# DRIVE_MOTORS.net
KiCad netlist of a schematic drawn in Altium Designer
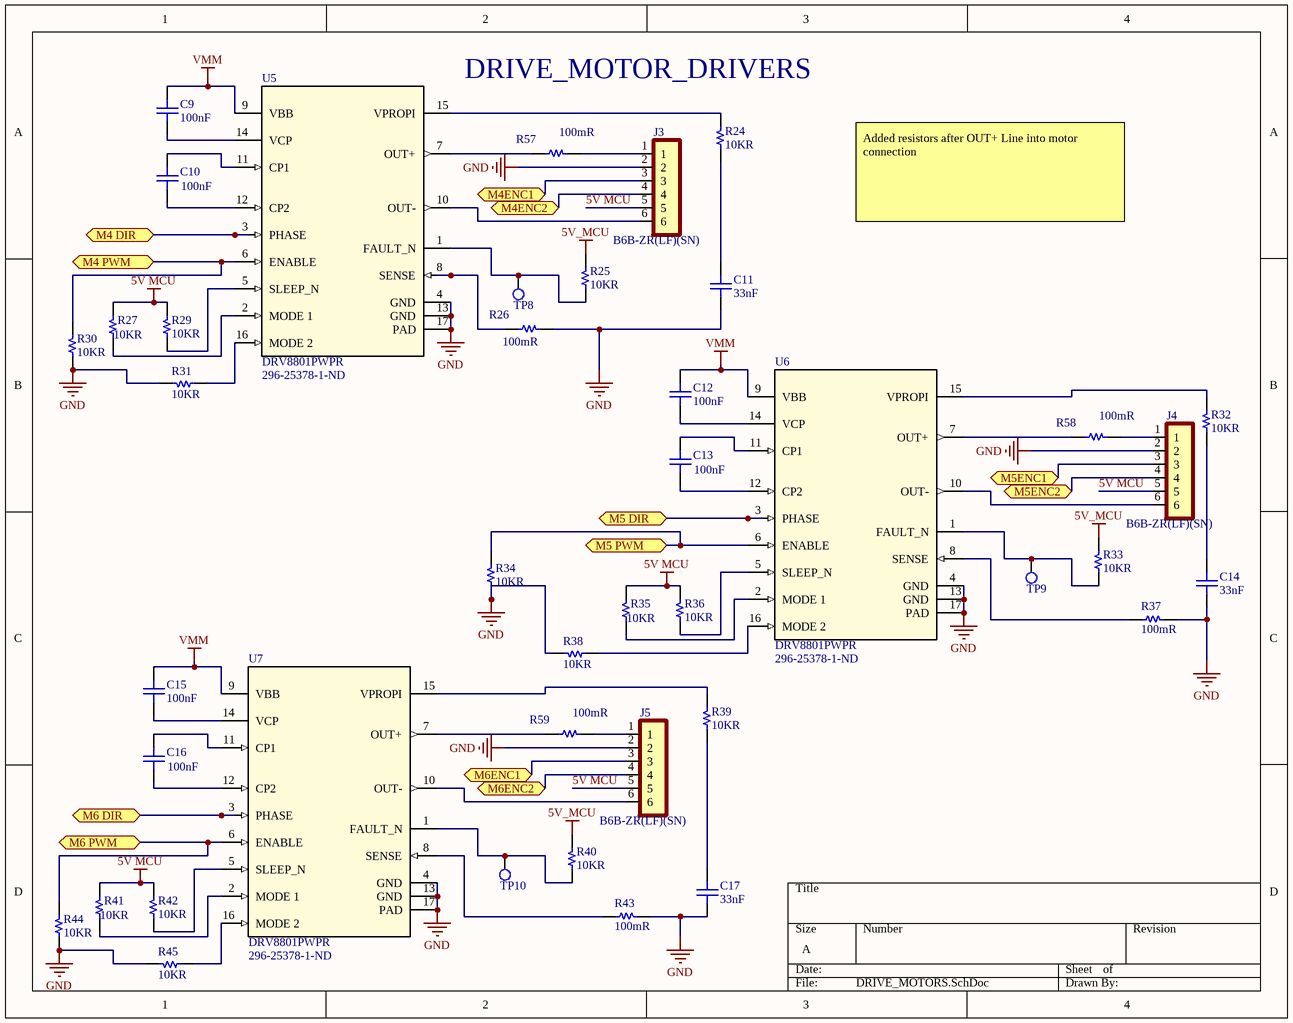
[diagram p0: DRIVE_MOTORS.SchDoc]

(export (version "E")
  (design (tool "Eeschema 10.0.6"))
  (components
    (comp (ref "C9")
      (value "100nF")
      (footprint "CAP_ADJ_0805")
      (description "CERAMIC CAPACITOR SMD 0805")
      (fields
        (field (name "MANUFACTURER") "KEMET")
        (field (name "MANUFACTURER PART NUMBER") "C0805C104J5RACAUTO")
      )
      (libsource (lib "ORI_MANIPULATOR_BRD") (part "CAP_ADJ_0805"))
    )
    (comp (ref "C10")
      (value "100nF")
      (footprint "CAP_ADJ_0805")
      (description "CERAMIC CAPACITOR SMD 0805")
      (fields
        (field (name "MANUFACTURER") "KEMET")
        (field (name "MANUFACTURER PART NUMBER") "C0805C104J5RACAUTO")
      )
      (libsource (lib "ORI_MANIPULATOR_BRD") (part "CAP_ADJ_0805"))
    )
    (comp (ref "C11")
      (value "33nF")
      (footprint "CAP_ADJ_0805")
      (description "CERAMIC CAPACITOR SMD 0805")
      (fields
        (field (name "MANUFACTURER") "Samsung")
        (field (name "MANUFACTURER PART NUMBER") "CL21B333JBANNNC")
      )
      (libsource (lib "ORI_MANIPULATOR_BRD") (part "CAP_ADJ_0805"))
    )
    (comp (ref "C12")
      (value "100nF")
      (footprint "CAP_ADJ_0805")
      (description "CERAMIC CAPACITOR SMD 0805")
      (fields
        (field (name "MANUFACTURER") "KEMET")
        (field (name "MANUFACTURER PART NUMBER") "C0805C104J5RACAUTO")
      )
      (libsource (lib "ORI_MANIPULATOR_BRD") (part "CAP_ADJ_0805"))
    )
    (comp (ref "C13")
      (value "100nF")
      (footprint "CAP_ADJ_0805")
      (description "CERAMIC CAPACITOR SMD 0805")
      (fields
        (field (name "MANUFACTURER") "KEMET")
        (field (name "MANUFACTURER PART NUMBER") "C0805C104J5RACAUTO")
      )
      (libsource (lib "ORI_MANIPULATOR_BRD") (part "CAP_ADJ_0805"))
    )
    (comp (ref "C14")
      (value "33nF")
      (footprint "CAP_ADJ_0805")
      (description "CERAMIC CAPACITOR SMD 0805")
      (fields
        (field (name "MANUFACTURER") "Samsung")
        (field (name "MANUFACTURER PART NUMBER") "CL21B333JBANNNC")
      )
      (libsource (lib "ORI_MANIPULATOR_BRD") (part "CAP_ADJ_0805"))
    )
    (comp (ref "C15")
      (value "100nF")
      (footprint "CAP_ADJ_0805")
      (description "CERAMIC CAPACITOR SMD 0805")
      (fields
        (field (name "MANUFACTURER") "KEMET")
        (field (name "MANUFACTURER PART NUMBER") "C0805C104J5RACAUTO")
      )
      (libsource (lib "ORI_MANIPULATOR_BRD") (part "CAP_ADJ_0805"))
    )
    (comp (ref "C16")
      (value "100nF")
      (footprint "CAP_ADJ_0805")
      (description "CERAMIC CAPACITOR SMD 0805")
      (fields
        (field (name "MANUFACTURER") "KEMET")
        (field (name "MANUFACTURER PART NUMBER") "C0805C104J5RACAUTO")
      )
      (libsource (lib "ORI_MANIPULATOR_BRD") (part "CAP_ADJ_0805"))
    )
    (comp (ref "C17")
      (value "33nF")
      (footprint "CAP_ADJ_0805")
      (description "CERAMIC CAPACITOR SMD 0805")
      (fields
        (field (name "MANUFACTURER") "Samsung")
        (field (name "MANUFACTURER PART NUMBER") "CL21B333JBANNNC")
      )
      (libsource (lib "ORI_MANIPULATOR_BRD") (part "CAP_ADJ_0805"))
    )
    (comp (ref "J3")
      (value "B6B-ZR(LF)(SN)")
      (footprint "SnapEDApcb:JST_B6B-ZR(LF)(SN)")
      (description "Connector Header Through Hole 6 position 0.059 _1.50mm_")
      (fields (field (name "MF") "JST Sales") (field (name "MP") "B6B-ZR_LF__SN_"))
      (libsource (lib "SnapEDAsch") (part "B6B-ZR(LF)(SN)"))
    )
    (comp (ref "J4")
      (value "B6B-ZR(LF)(SN)")
      (footprint "SnapEDApcb:JST_B6B-ZR(LF)(SN)")
      (description "Connector Header Through Hole 6 position 0.059 _1.50mm_")
      (fields (field (name "MF") "JST Sales") (field (name "MP") "B6B-ZR_LF__SN_"))
      (libsource (lib "SnapEDAsch") (part "B6B-ZR(LF)(SN)"))
    )
    (comp (ref "J5")
      (value "B6B-ZR(LF)(SN)")
      (footprint "SnapEDApcb:JST_B6B-ZR(LF)(SN)")
      (description "Connector Header Through Hole 6 position 0.059 _1.50mm_")
      (fields (field (name "MF") "JST Sales") (field (name "MP") "B6B-ZR_LF__SN_"))
      (libsource (lib "SnapEDAsch") (part "B6B-ZR(LF)(SN)"))
    )
    (comp (ref "R24")
      (value "10KR")
      (footprint "RES_ADJ_0805_YAGEO")
      (description "RESISTOR 0805 YAGEO")
      (fields
        (field (name "MANUFACTURER") "Yageo")
        (field (name "MANUFACTURER PART NUMBER") "RC0805JR-0710KL")
      )
      (libsource (lib "ORI_MANIPULATOR_BRD") (part "RES_ADJ_0805"))
    )
    (comp (ref "R25")
      (value "10KR")
      (footprint "RES_ADJ_0805_YAGEO")
      (description "RESISTOR 0805 YAGEO")
      (fields
        (field (name "MANUFACTURER") "Yageo")
        (field (name "MANUFACTURER PART NUMBER") "RC0805JR-0710KL")
      )
      (libsource (lib "ORI_MANIPULATOR_BRD") (part "RES_ADJ_0805"))
    )
    (comp (ref "R26")
      (value "100mR")
      (footprint "RES_ADJ_0805_YAGEO")
      (description "RESISTOR 0805 YAGEO")
      (fields
        (field (name "MANUFACTURER") "Panasonic")
        (field (name "MANUFACTURER PART NUMBER") "ERJ-6DSFR10V")
      )
      (libsource (lib "ORI_MANIPULATOR_BRD") (part "RES_ADJ_0805"))
    )
    (comp (ref "R27")
      (value "10KR")
      (footprint "RES_ADJ_0805_YAGEO")
      (description "RESISTOR 0805 YAGEO")
      (fields
        (field (name "MANUFACTURER") "Yageo")
        (field (name "MANUFACTURER PART NUMBER") "RC0805JR-0710KL")
      )
      (libsource (lib "ORI_MANIPULATOR_BRD") (part "RES_ADJ_0805"))
    )
    (comp (ref "R29")
      (value "10KR")
      (footprint "RES_ADJ_0805_YAGEO")
      (description "RESISTOR 0805 YAGEO")
      (fields
        (field (name "MANUFACTURER") "Yageo")
        (field (name "MANUFACTURER PART NUMBER") "RC0805JR-0710KL")
      )
      (libsource (lib "ORI_MANIPULATOR_BRD") (part "RES_ADJ_0805"))
    )
    (comp (ref "R30")
      (value "10KR")
      (footprint "RES_ADJ_0805_YAGEO")
      (description "RESISTOR 0805 YAGEO")
      (fields
        (field (name "MANUFACTURER") "Yageo")
        (field (name "MANUFACTURER PART NUMBER") "RC0805JR-0710KL")
      )
      (libsource (lib "ORI_MANIPULATOR_BRD") (part "RES_ADJ_0805"))
    )
    (comp (ref "R31")
      (value "10KR")
      (footprint "RES_ADJ_0805_YAGEO")
      (description "RESISTOR 0805 YAGEO")
      (fields
        (field (name "MANUFACTURER") "Yageo")
        (field (name "MANUFACTURER PART NUMBER") "RC0805JR-0710KL")
      )
      (libsource (lib "ORI_MANIPULATOR_BRD") (part "RES_ADJ_0805"))
    )
    (comp (ref "R32")
      (value "10KR")
      (footprint "RES_ADJ_0805_YAGEO")
      (description "RESISTOR 0805 YAGEO")
      (fields
        (field (name "MANUFACTURER") "Yageo")
        (field (name "MANUFACTURER PART NUMBER") "RC0805JR-0710KL")
      )
      (libsource (lib "ORI_MANIPULATOR_BRD") (part "RES_ADJ_0805"))
    )
    (comp (ref "R33")
      (value "10KR")
      (footprint "RES_ADJ_0805_YAGEO")
      (description "RESISTOR 0805 YAGEO")
      (fields
        (field (name "MANUFACTURER") "Yageo")
        (field (name "MANUFACTURER PART NUMBER") "RC0805JR-0710KL")
      )
      (libsource (lib "ORI_MANIPULATOR_BRD") (part "RES_ADJ_0805"))
    )
    (comp (ref "R34")
      (value "10KR")
      (footprint "RES_ADJ_0805_YAGEO")
      (description "RESISTOR 0805 YAGEO")
      (fields
        (field (name "MANUFACTURER") "Yageo")
        (field (name "MANUFACTURER PART NUMBER") "RC0805JR-0710KL")
      )
      (libsource (lib "ORI_MANIPULATOR_BRD") (part "RES_ADJ_0805"))
    )
    (comp (ref "R35")
      (value "10KR")
      (footprint "RES_ADJ_0805_YAGEO")
      (description "RESISTOR 0805 YAGEO")
      (fields
        (field (name "MANUFACTURER") "Yageo")
        (field (name "MANUFACTURER PART NUMBER") "RC0805JR-0710KL")
      )
      (libsource (lib "ORI_MANIPULATOR_BRD") (part "RES_ADJ_0805"))
    )
    (comp (ref "R36")
      (value "10KR")
      (footprint "RES_ADJ_0805_YAGEO")
      (description "RESISTOR 0805 YAGEO")
      (fields
        (field (name "MANUFACTURER") "Yageo")
        (field (name "MANUFACTURER PART NUMBER") "RC0805JR-0710KL")
      )
      (libsource (lib "ORI_MANIPULATOR_BRD") (part "RES_ADJ_0805"))
    )
    (comp (ref "R37")
      (value "100mR")
      (footprint "RES_ADJ_0805_YAGEO")
      (description "RESISTOR 0805 YAGEO")
      (fields
        (field (name "MANUFACTURER") "Panasonic")
        (field (name "MANUFACTURER PART NUMBER") "ERJ-6DSFR10V")
      )
      (libsource (lib "ORI_MANIPULATOR_BRD") (part "RES_ADJ_0805"))
    )
    (comp (ref "R38")
      (value "10KR")
      (footprint "RES_ADJ_0805_YAGEO")
      (description "RESISTOR 0805 YAGEO")
      (fields
        (field (name "MANUFACTURER") "Yageo")
        (field (name "MANUFACTURER PART NUMBER") "RC0805JR-0710KL")
      )
      (libsource (lib "ORI_MANIPULATOR_BRD") (part "RES_ADJ_0805"))
    )
    (comp (ref "R39")
      (value "10KR")
      (footprint "RES_ADJ_0805_YAGEO")
      (description "RESISTOR 0805 YAGEO")
      (fields
        (field (name "MANUFACTURER") "Yageo")
        (field (name "MANUFACTURER PART NUMBER") "RC0805JR-0710KL")
      )
      (libsource (lib "ORI_MANIPULATOR_BRD") (part "RES_ADJ_0805"))
    )
    (comp (ref "R40")
      (value "10KR")
      (footprint "RES_ADJ_0805_YAGEO")
      (description "RESISTOR 0805 YAGEO")
      (fields
        (field (name "MANUFACTURER") "Yageo")
        (field (name "MANUFACTURER PART NUMBER") "RC0805JR-0710KL")
      )
      (libsource (lib "ORI_MANIPULATOR_BRD") (part "RES_ADJ_0805"))
    )
    (comp (ref "R41")
      (value "10KR")
      (footprint "RES_ADJ_0805_YAGEO")
      (description "RESISTOR 0805 YAGEO")
      (fields
        (field (name "MANUFACTURER") "Yageo")
        (field (name "MANUFACTURER PART NUMBER") "RC0805JR-0710KL")
      )
      (libsource (lib "ORI_MANIPULATOR_BRD") (part "RES_ADJ_0805"))
    )
    (comp (ref "R42")
      (value "10KR")
      (footprint "RES_ADJ_0805_YAGEO")
      (description "RESISTOR 0805 YAGEO")
      (fields
        (field (name "MANUFACTURER") "Yageo")
        (field (name "MANUFACTURER PART NUMBER") "RC0805JR-0710KL")
      )
      (libsource (lib "ORI_MANIPULATOR_BRD") (part "RES_ADJ_0805"))
    )
    (comp (ref "R43")
      (value "100mR")
      (footprint "RES_ADJ_0805_YAGEO")
      (description "RESISTOR 0805 YAGEO")
      (fields
        (field (name "MANUFACTURER") "Panasonic")
        (field (name "MANUFACTURER PART NUMBER") "ERJ-6DSFR10V")
      )
      (libsource (lib "ORI_MANIPULATOR_BRD") (part "RES_ADJ_0805"))
    )
    (comp (ref "R44")
      (value "10KR")
      (footprint "RES_ADJ_0805_YAGEO")
      (description "RESISTOR 0805 YAGEO")
      (fields
        (field (name "MANUFACTURER") "Yageo")
        (field (name "MANUFACTURER PART NUMBER") "RC0805JR-0710KL")
      )
      (libsource (lib "ORI_MANIPULATOR_BRD") (part "RES_ADJ_0805"))
    )
    (comp (ref "R45")
      (value "10KR")
      (footprint "RES_ADJ_0805_YAGEO")
      (description "RESISTOR 0805 YAGEO")
      (fields
        (field (name "MANUFACTURER") "Yageo")
        (field (name "MANUFACTURER PART NUMBER") "RC0805JR-0710KL")
      )
      (libsource (lib "ORI_MANIPULATOR_BRD") (part "RES_ADJ_0805"))
    )
    (comp (ref "R57")
      (value "100mR")
      (footprint "RES_ADJ_0805_YAGEO")
      (description "RESISTOR 0805 YAGEO")
      (fields
        (field (name "MANUFACTURER") "Panasonic")
        (field (name "MANUFACTURER PART NUMBER") "ERJ-6DSFR10V")
      )
      (libsource (lib "ORI_MANIPULATOR_BRD") (part "RES_ADJ_0805"))
    )
    (comp (ref "R58")
      (value "100mR")
      (footprint "RES_ADJ_0805_YAGEO")
      (description "RESISTOR 0805 YAGEO")
      (fields
        (field (name "MANUFACTURER") "Panasonic")
        (field (name "MANUFACTURER PART NUMBER") "ERJ-6DSFR10V")
      )
      (libsource (lib "ORI_MANIPULATOR_BRD") (part "RES_ADJ_0805"))
    )
    (comp (ref "R59")
      (value "100mR")
      (footprint "RES_ADJ_0805_YAGEO")
      (description "RESISTOR 0805 YAGEO")
      (fields
        (field (name "MANUFACTURER") "Panasonic")
        (field (name "MANUFACTURER PART NUMBER") "ERJ-6DSFR10V")
      )
      (libsource (lib "ORI_MANIPULATOR_BRD") (part "RES_ADJ_0805"))
    )
    (comp (ref "TP8")
      (value "TEST_POINT")
      (footprint "TEST_POINT")
      (description "TEST POINT PAD")
      (libsource (lib "ORI_MANIPULATOR_BRD") (part "TEST_POINT"))
    )
    (comp (ref "TP9")
      (value "TEST_POINT")
      (footprint "TEST_POINT")
      (description "TEST POINT PAD")
      (libsource (lib "ORI_MANIPULATOR_BRD") (part "TEST_POINT"))
    )
    (comp (ref "TP10")
      (value "TEST_POINT")
      (footprint "TEST_POINT")
      (description "TEST POINT PAD")
      (libsource (lib "ORI_MANIPULATOR_BRD") (part "TEST_POINT"))
    )
    (comp (ref "U5")
      (value "DRV8801PWPR")
      (footprint "PWP0016B_N")
      (description "IC MOTOR DRIVER PAR 16HTSSOP")
      (fields
        (field (name "MANUFACTURER") "Texas Instruments")
        (field (name "SUPPLIER PART NUMBER 1") "296-25378-1-ND")
      )
      (libsource (lib "ORI_MANIPULATOR_BRD") (part "DRV8801PWPR"))
    )
    (comp (ref "U6")
      (value "DRV8801PWPR")
      (footprint "PWP0016B_N")
      (description "IC MOTOR DRIVER PAR 16HTSSOP")
      (fields
        (field (name "MANUFACTURER") "Texas Instruments")
        (field (name "SUPPLIER PART NUMBER 1") "296-25378-1-ND")
      )
      (libsource (lib "ORI_MANIPULATOR_BRD") (part "DRV8801PWPR"))
    )
    (comp (ref "U7")
      (value "DRV8801PWPR")
      (footprint "PWP0016B_N")
      (description "IC MOTOR DRIVER PAR 16HTSSOP")
      (fields
        (field (name "MANUFACTURER") "Texas Instruments")
        (field (name "SUPPLIER PART NUMBER 1") "296-25378-1-ND")
      )
      (libsource (lib "ORI_MANIPULATOR_BRD") (part "DRV8801PWPR"))
    )
  )
  (nets
    (net (code "1") (name "/M4 DIR") (class "Default")
      (node (ref "U5") (pin "3") (pinfunction "PHASE_3") (pintype "input"))
    )
    (net (code "2") (name "/M4 PWM") (class "Default")
      (node (ref "R30") (pin "2") (pinfunction "2_2") (pintype "passive"))
      (node (ref "U5") (pin "6") (pinfunction "ENABLE_6") (pintype "input"))
    )
    (net (code "3") (name "/M4ENC1") (class "Default")
      (node (ref "J3") (pin "3") (pinfunction "3_3") (pintype "passive"))
    )
    (net (code "4") (name "/M4ENC2") (class "Default")
      (node (ref "J3") (pin "4") (pinfunction "4_4") (pintype "passive"))
    )
    (net (code "5") (name "/M5 DIR") (class "Default")
      (node (ref "U6") (pin "3") (pinfunction "PHASE_3") (pintype "input"))
    )
    (net (code "6") (name "/M5 PWM") (class "Default")
      (node (ref "R34") (pin "2") (pinfunction "2_2") (pintype "passive"))
      (node (ref "U6") (pin "6") (pinfunction "ENABLE_6") (pintype "input"))
    )
    (net (code "7") (name "/M5ENC1") (class "Default")
      (node (ref "J4") (pin "3") (pinfunction "3_3") (pintype "passive"))
    )
    (net (code "8") (name "/M5ENC2") (class "Default")
      (node (ref "J4") (pin "4") (pinfunction "4_4") (pintype "passive"))
    )
    (net (code "9") (name "/M6 DIR") (class "Default")
      (node (ref "U7") (pin "3") (pinfunction "PHASE_3") (pintype "input"))
    )
    (net (code "10") (name "/M6 PWM") (class "Default")
      (node (ref "R44") (pin "2") (pinfunction "2_2") (pintype "passive"))
      (node (ref "U7") (pin "6") (pinfunction "ENABLE_6") (pintype "input"))
    )
    (net (code "11") (name "/M6ENC1") (class "Default")
      (node (ref "J5") (pin "3") (pinfunction "3_3") (pintype "passive"))
    )
    (net (code "12") (name "/M6ENC2") (class "Default")
      (node (ref "J5") (pin "4") (pinfunction "4_4") (pintype "passive"))
    )
    (net (code "13") (name "5V MCU") (class "Default")
      (node (ref "J3") (pin "5") (pinfunction "5_5") (pintype "passive"))
      (node (ref "J4") (pin "5") (pinfunction "5_5") (pintype "passive"))
      (node (ref "J5") (pin "5") (pinfunction "5_5") (pintype "passive"))
      (node (ref "R27") (pin "2") (pinfunction "2_2") (pintype "passive"))
      (node (ref "R29") (pin "2") (pinfunction "2_2") (pintype "passive"))
      (node (ref "R35") (pin "2") (pinfunction "2_2") (pintype "passive"))
      (node (ref "R36") (pin "2") (pinfunction "2_2") (pintype "passive"))
      (node (ref "R41") (pin "2") (pinfunction "2_2") (pintype "passive"))
      (node (ref "R42") (pin "2") (pinfunction "2_2") (pintype "passive"))
    )
    (net (code "14") (name "5V_MCU") (class "Default")
      (node (ref "R25") (pin "2") (pinfunction "2_2") (pintype "passive"))
      (node (ref "R33") (pin "2") (pinfunction "2_2") (pintype "passive"))
      (node (ref "R40") (pin "2") (pinfunction "2_2") (pintype "passive"))
    )
    (net (code "15") (name "GND") (class "Default")
      (node (ref "C11") (pin "1") (pinfunction "1_1") (pintype "passive"))
      (node (ref "C14") (pin "1") (pinfunction "1_1") (pintype "passive"))
      (node (ref "C17") (pin "1") (pinfunction "1_1") (pintype "passive"))
      (node (ref "J3") (pin "2") (pinfunction "2_2") (pintype "passive"))
      (node (ref "J4") (pin "2") (pinfunction "2_2") (pintype "passive"))
      (node (ref "J5") (pin "2") (pinfunction "2_2") (pintype "passive"))
      (node (ref "R26") (pin "2") (pinfunction "2_2") (pintype "passive"))
      (node (ref "R30") (pin "1") (pinfunction "1_1") (pintype "passive"))
      (node (ref "R31") (pin "2") (pinfunction "2_2") (pintype "passive"))
      (node (ref "R34") (pin "1") (pinfunction "1_1") (pintype "passive"))
      (node (ref "R37") (pin "2") (pinfunction "2_2") (pintype "passive"))
      (node (ref "R38") (pin "2") (pinfunction "2_2") (pintype "passive"))
      (node (ref "R43") (pin "2") (pinfunction "2_2") (pintype "passive"))
      (node (ref "R44") (pin "1") (pinfunction "1_1") (pintype "passive"))
      (node (ref "R45") (pin "2") (pinfunction "2_2") (pintype "passive"))
      (node (ref "U5") (pin "13") (pinfunction "GND_13") (pintype "power_in"))
      (node (ref "U5") (pin "17") (pinfunction "PAD_17") (pintype "power_in"))
      (node (ref "U5") (pin "4") (pinfunction "GND_4") (pintype "power_in"))
      (node (ref "U6") (pin "13") (pinfunction "GND_13") (pintype "power_in"))
      (node (ref "U6") (pin "17") (pinfunction "PAD_17") (pintype "power_in"))
      (node (ref "U6") (pin "4") (pinfunction "GND_4") (pintype "power_in"))
      (node (ref "U7") (pin "13") (pinfunction "GND_13") (pintype "power_in"))
      (node (ref "U7") (pin "17") (pinfunction "PAD_17") (pintype "power_in"))
      (node (ref "U7") (pin "4") (pinfunction "GND_4") (pintype "power_in"))
    )
    (net (code "16") (name "Net-(C11-Pad2)") (class "Default")
      (node (ref "C11") (pin "2") (pinfunction "2_2") (pintype "passive"))
      (node (ref "R24") (pin "1") (pinfunction "1_1") (pintype "passive"))
    )
    (net (code "17") (name "Net-(C14-Pad2)") (class "Default")
      (node (ref "C14") (pin "2") (pinfunction "2_2") (pintype "passive"))
      (node (ref "R32") (pin "1") (pinfunction "1_1") (pintype "passive"))
    )
    (net (code "18") (name "Net-(C17-Pad2)") (class "Default")
      (node (ref "C17") (pin "2") (pinfunction "2_2") (pintype "passive"))
      (node (ref "R39") (pin "1") (pinfunction "1_1") (pintype "passive"))
    )
    (net (code "19") (name "Net-(J3-Pad1)") (class "Default")
      (node (ref "J3") (pin "1") (pinfunction "1_1") (pintype "passive"))
      (node (ref "R57") (pin "2") (pinfunction "2_2") (pintype "passive"))
    )
    (net (code "20") (name "Net-(J4-Pad1)") (class "Default")
      (node (ref "J4") (pin "1") (pinfunction "1_1") (pintype "passive"))
      (node (ref "R58") (pin "2") (pinfunction "2_2") (pintype "passive"))
    )
    (net (code "21") (name "Net-(J5-Pad1)") (class "Default")
      (node (ref "J5") (pin "1") (pinfunction "1_1") (pintype "passive"))
      (node (ref "R59") (pin "2") (pinfunction "2_2") (pintype "passive"))
    )
    (net (code "22") (name "Net-(U5-CP1)") (class "Default")
      (node (ref "C10") (pin "2") (pinfunction "2_2") (pintype "passive"))
      (node (ref "U5") (pin "11") (pinfunction "CP1_11") (pintype "input"))
    )
    (net (code "23") (name "Net-(U5-CP2)") (class "Default")
      (node (ref "C10") (pin "1") (pinfunction "1_1") (pintype "passive"))
      (node (ref "U5") (pin "12") (pinfunction "CP2_12") (pintype "input"))
    )
    (net (code "24") (name "Net-(U5-FAULT_N)") (class "Default")
      (node (ref "R25") (pin "1") (pinfunction "1_1") (pintype "passive"))
      (node (ref "TP8") (pin "1") (pinfunction "1_1") (pintype "passive"))
      (node (ref "U5") (pin "1") (pinfunction "FAULT_N_1") (pintype "open_collector"))
    )
    (net (code "25") (name "Net-(U5-MODE_1)") (class "Default")
      (node (ref "R27") (pin "1") (pinfunction "1_1") (pintype "passive"))
      (node (ref "U5") (pin "2") (pinfunction "MODE_1_2") (pintype "input"))
    )
    (net (code "26") (name "Net-(U5-MODE_2)") (class "Default")
      (node (ref "R31") (pin "1") (pinfunction "1_1") (pintype "passive"))
      (node (ref "U5") (pin "16") (pinfunction "MODE_2_16") (pintype "input"))
    )
    (net (code "27") (name "Net-(U5-OUT+)") (class "Default")
      (node (ref "R57") (pin "1") (pinfunction "1_1") (pintype "passive"))
      (node (ref "U5") (pin "7") (pinfunction "OUT+_7") (pintype "output"))
    )
    (net (code "28") (name "Net-(U5-OUT-)") (class "Default")
      (node (ref "J3") (pin "6") (pinfunction "6_6") (pintype "passive"))
      (node (ref "U5") (pin "10") (pinfunction "OUT-_10") (pintype "output"))
    )
    (net (code "29") (name "Net-(U5-SENSE)") (class "Default")
      (node (ref "R26") (pin "1") (pinfunction "1_1") (pintype "passive"))
      (node (ref "U5") (pin "8") (pinfunction "SENSE_8") (pintype "input"))
    )
    (net (code "30") (name "Net-(U5-SLEEP_N)") (class "Default")
      (node (ref "R29") (pin "1") (pinfunction "1_1") (pintype "passive"))
      (node (ref "U5") (pin "5") (pinfunction "SLEEP_N_5") (pintype "input"))
    )
    (net (code "31") (name "Net-(U5-VCP)") (class "Default")
      (node (ref "C9") (pin "1") (pinfunction "1_1") (pintype "passive"))
      (node (ref "U5") (pin "14") (pinfunction "VCP_14") (pintype "passive"))
    )
    (net (code "32") (name "Net-(U5-VPROPI)") (class "Default")
      (node (ref "R24") (pin "2") (pinfunction "2_2") (pintype "passive"))
      (node (ref "U5") (pin "15") (pinfunction "VPROPI_15") (pintype "power_in"))
    )
    (net (code "33") (name "Net-(U6-CP1)") (class "Default")
      (node (ref "C13") (pin "2") (pinfunction "2_2") (pintype "passive"))
      (node (ref "U6") (pin "11") (pinfunction "CP1_11") (pintype "input"))
    )
    (net (code "34") (name "Net-(U6-CP2)") (class "Default")
      (node (ref "C13") (pin "1") (pinfunction "1_1") (pintype "passive"))
      (node (ref "U6") (pin "12") (pinfunction "CP2_12") (pintype "input"))
    )
    (net (code "35") (name "Net-(U6-FAULT_N)") (class "Default")
      (node (ref "R33") (pin "1") (pinfunction "1_1") (pintype "passive"))
      (node (ref "TP9") (pin "1") (pinfunction "1_1") (pintype "passive"))
      (node (ref "U6") (pin "1") (pinfunction "FAULT_N_1") (pintype "open_collector"))
    )
    (net (code "36") (name "Net-(U6-MODE_1)") (class "Default")
      (node (ref "R35") (pin "1") (pinfunction "1_1") (pintype "passive"))
      (node (ref "U6") (pin "2") (pinfunction "MODE_1_2") (pintype "input"))
    )
    (net (code "37") (name "Net-(U6-MODE_2)") (class "Default")
      (node (ref "R38") (pin "1") (pinfunction "1_1") (pintype "passive"))
      (node (ref "U6") (pin "16") (pinfunction "MODE_2_16") (pintype "input"))
    )
    (net (code "38") (name "Net-(U6-OUT+)") (class "Default")
      (node (ref "R58") (pin "1") (pinfunction "1_1") (pintype "passive"))
      (node (ref "U6") (pin "7") (pinfunction "OUT+_7") (pintype "output"))
    )
    (net (code "39") (name "Net-(U6-OUT-)") (class "Default")
      (node (ref "J4") (pin "6") (pinfunction "6_6") (pintype "passive"))
      (node (ref "U6") (pin "10") (pinfunction "OUT-_10") (pintype "output"))
    )
    (net (code "40") (name "Net-(U6-SENSE)") (class "Default")
      (node (ref "R37") (pin "1") (pinfunction "1_1") (pintype "passive"))
      (node (ref "U6") (pin "8") (pinfunction "SENSE_8") (pintype "input"))
    )
    (net (code "41") (name "Net-(U6-SLEEP_N)") (class "Default")
      (node (ref "R36") (pin "1") (pinfunction "1_1") (pintype "passive"))
      (node (ref "U6") (pin "5") (pinfunction "SLEEP_N_5") (pintype "input"))
    )
    (net (code "42") (name "Net-(U6-VCP)") (class "Default")
      (node (ref "C12") (pin "1") (pinfunction "1_1") (pintype "passive"))
      (node (ref "U6") (pin "14") (pinfunction "VCP_14") (pintype "passive"))
    )
    (net (code "43") (name "Net-(U6-VPROPI)") (class "Default")
      (node (ref "R32") (pin "2") (pinfunction "2_2") (pintype "passive"))
      (node (ref "U6") (pin "15") (pinfunction "VPROPI_15") (pintype "power_in"))
    )
    (net (code "44") (name "Net-(U7-CP1)") (class "Default")
      (node (ref "C16") (pin "2") (pinfunction "2_2") (pintype "passive"))
      (node (ref "U7") (pin "11") (pinfunction "CP1_11") (pintype "input"))
    )
    (net (code "45") (name "Net-(U7-CP2)") (class "Default")
      (node (ref "C16") (pin "1") (pinfunction "1_1") (pintype "passive"))
      (node (ref "U7") (pin "12") (pinfunction "CP2_12") (pintype "input"))
    )
    (net (code "46") (name "Net-(U7-FAULT_N)") (class "Default")
      (node (ref "R40") (pin "1") (pinfunction "1_1") (pintype "passive"))
      (node (ref "TP10") (pin "1") (pinfunction "1_1") (pintype "passive"))
      (node (ref "U7") (pin "1") (pinfunction "FAULT_N_1") (pintype "open_collector"))
    )
    (net (code "47") (name "Net-(U7-MODE_1)") (class "Default")
      (node (ref "R41") (pin "1") (pinfunction "1_1") (pintype "passive"))
      (node (ref "U7") (pin "2") (pinfunction "MODE_1_2") (pintype "input"))
    )
    (net (code "48") (name "Net-(U7-MODE_2)") (class "Default")
      (node (ref "R45") (pin "1") (pinfunction "1_1") (pintype "passive"))
      (node (ref "U7") (pin "16") (pinfunction "MODE_2_16") (pintype "input"))
    )
    (net (code "49") (name "Net-(U7-OUT+)") (class "Default")
      (node (ref "R59") (pin "1") (pinfunction "1_1") (pintype "passive"))
      (node (ref "U7") (pin "7") (pinfunction "OUT+_7") (pintype "output"))
    )
    (net (code "50") (name "Net-(U7-OUT-)") (class "Default")
      (node (ref "J5") (pin "6") (pinfunction "6_6") (pintype "passive"))
      (node (ref "U7") (pin "10") (pinfunction "OUT-_10") (pintype "output"))
    )
    (net (code "51") (name "Net-(U7-SENSE)") (class "Default")
      (node (ref "R43") (pin "1") (pinfunction "1_1") (pintype "passive"))
      (node (ref "U7") (pin "8") (pinfunction "SENSE_8") (pintype "input"))
    )
    (net (code "52") (name "Net-(U7-SLEEP_N)") (class "Default")
      (node (ref "R42") (pin "1") (pinfunction "1_1") (pintype "passive"))
      (node (ref "U7") (pin "5") (pinfunction "SLEEP_N_5") (pintype "input"))
    )
    (net (code "53") (name "Net-(U7-VCP)") (class "Default")
      (node (ref "C15") (pin "1") (pinfunction "1_1") (pintype "passive"))
      (node (ref "U7") (pin "14") (pinfunction "VCP_14") (pintype "passive"))
    )
    (net (code "54") (name "Net-(U7-VPROPI)") (class "Default")
      (node (ref "R39") (pin "2") (pinfunction "2_2") (pintype "passive"))
      (node (ref "U7") (pin "15") (pinfunction "VPROPI_15") (pintype "power_in"))
    )
    (net (code "55") (name "VMM") (class "Default")
      (node (ref "C12") (pin "2") (pinfunction "2_2") (pintype "passive"))
      (node (ref "C15") (pin "2") (pinfunction "2_2") (pintype "passive"))
      (node (ref "C9") (pin "2") (pinfunction "2_2") (pintype "passive"))
      (node (ref "U5") (pin "9") (pinfunction "VBB_9") (pintype "power_in"))
      (node (ref "U6") (pin "9") (pinfunction "VBB_9") (pintype "power_in"))
      (node (ref "U7") (pin "9") (pinfunction "VBB_9") (pintype "power_in"))
    )
  )
)
